# Backplane_v1.net
KiCad netlist of a schematic drawn in EAGLE
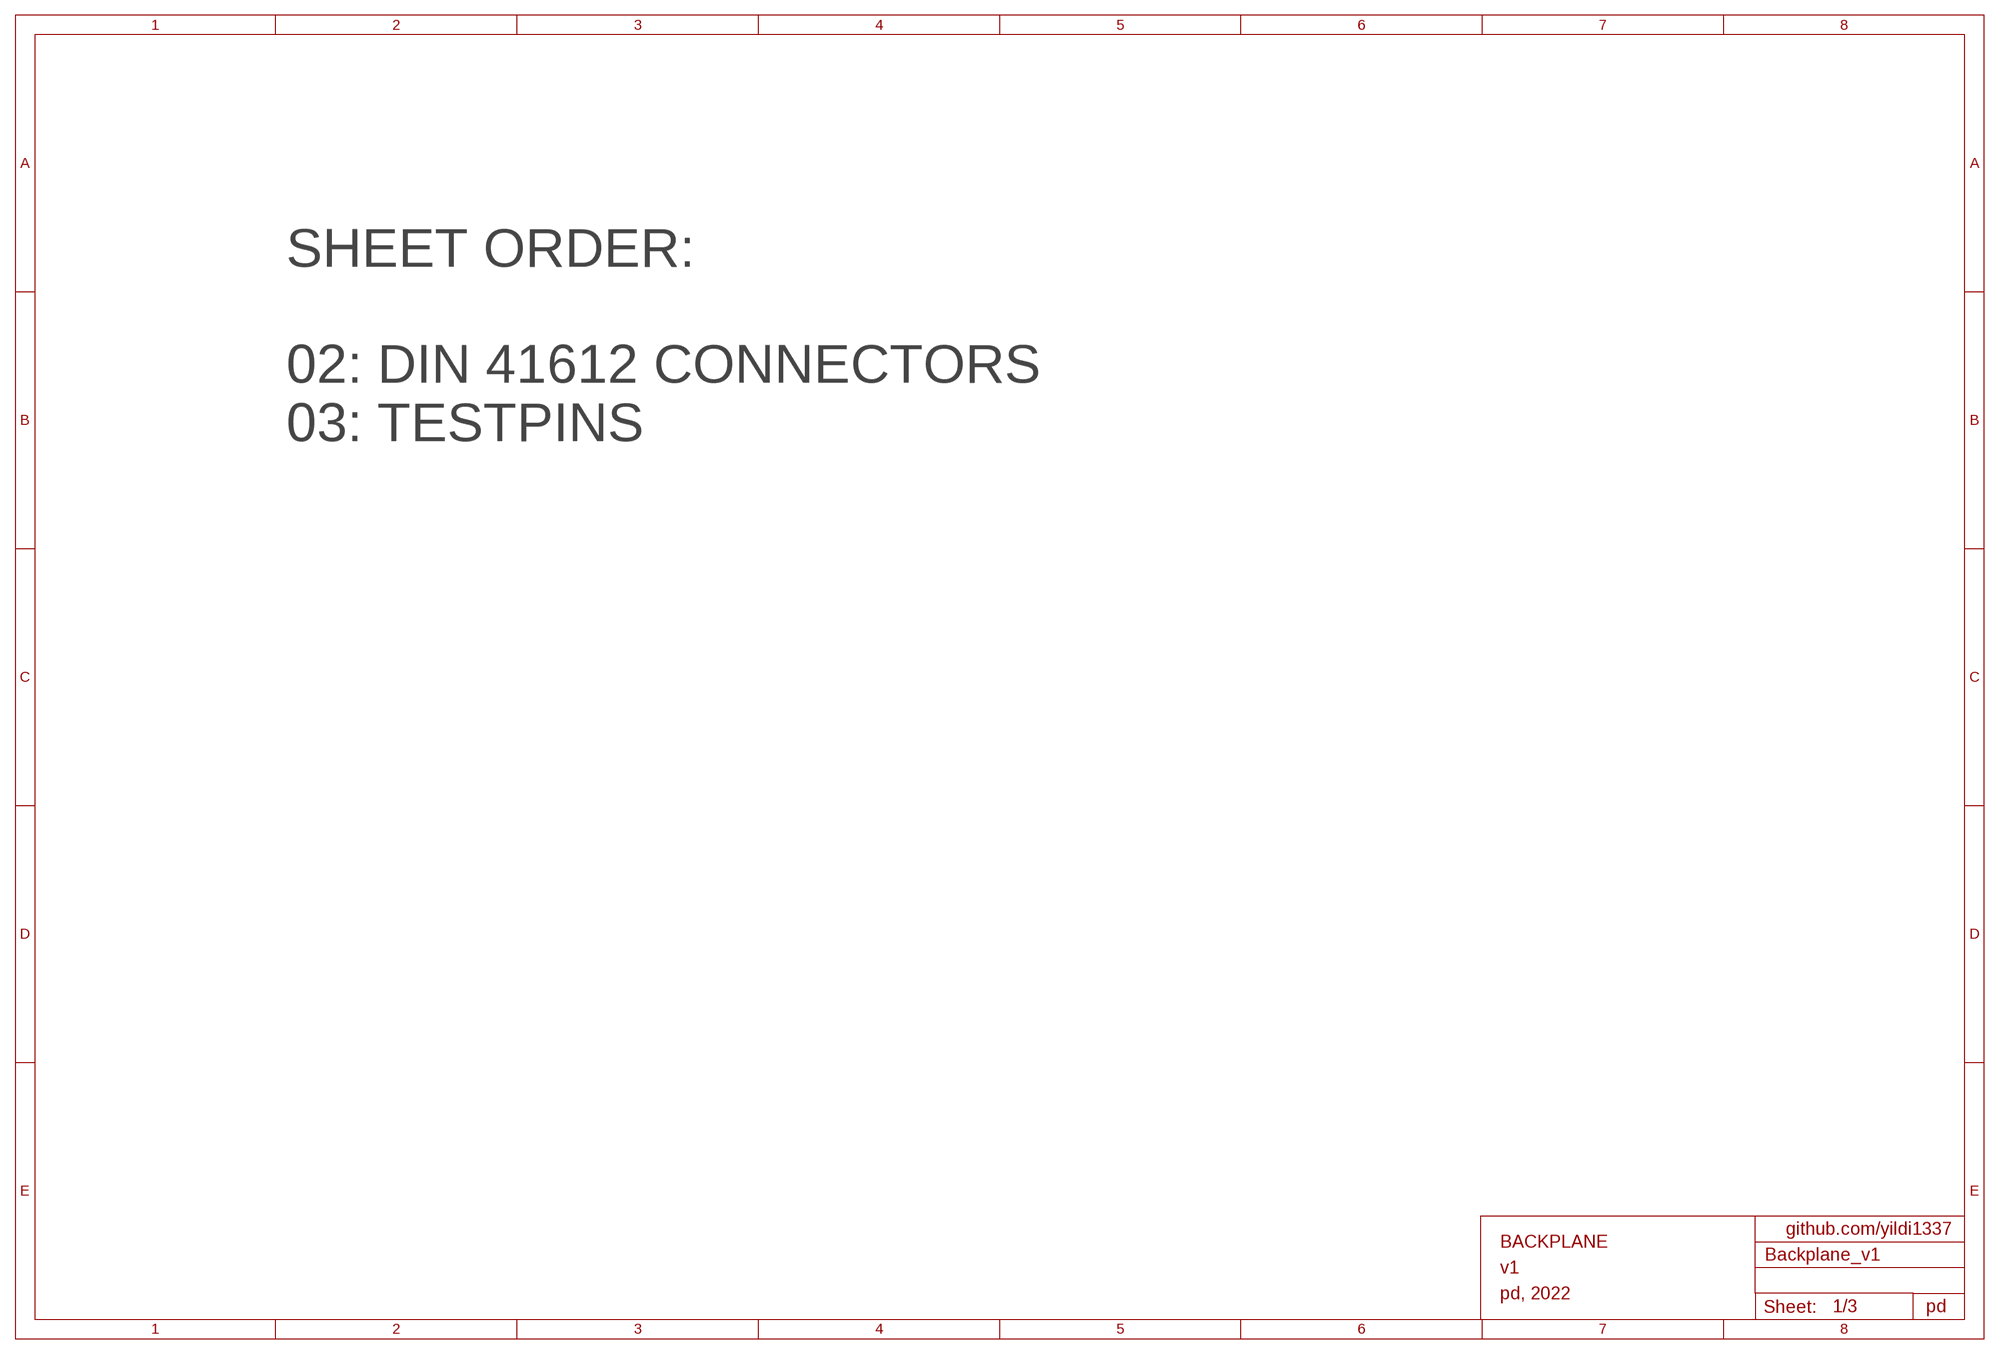
[diagram p0: schematic, sheet 1]
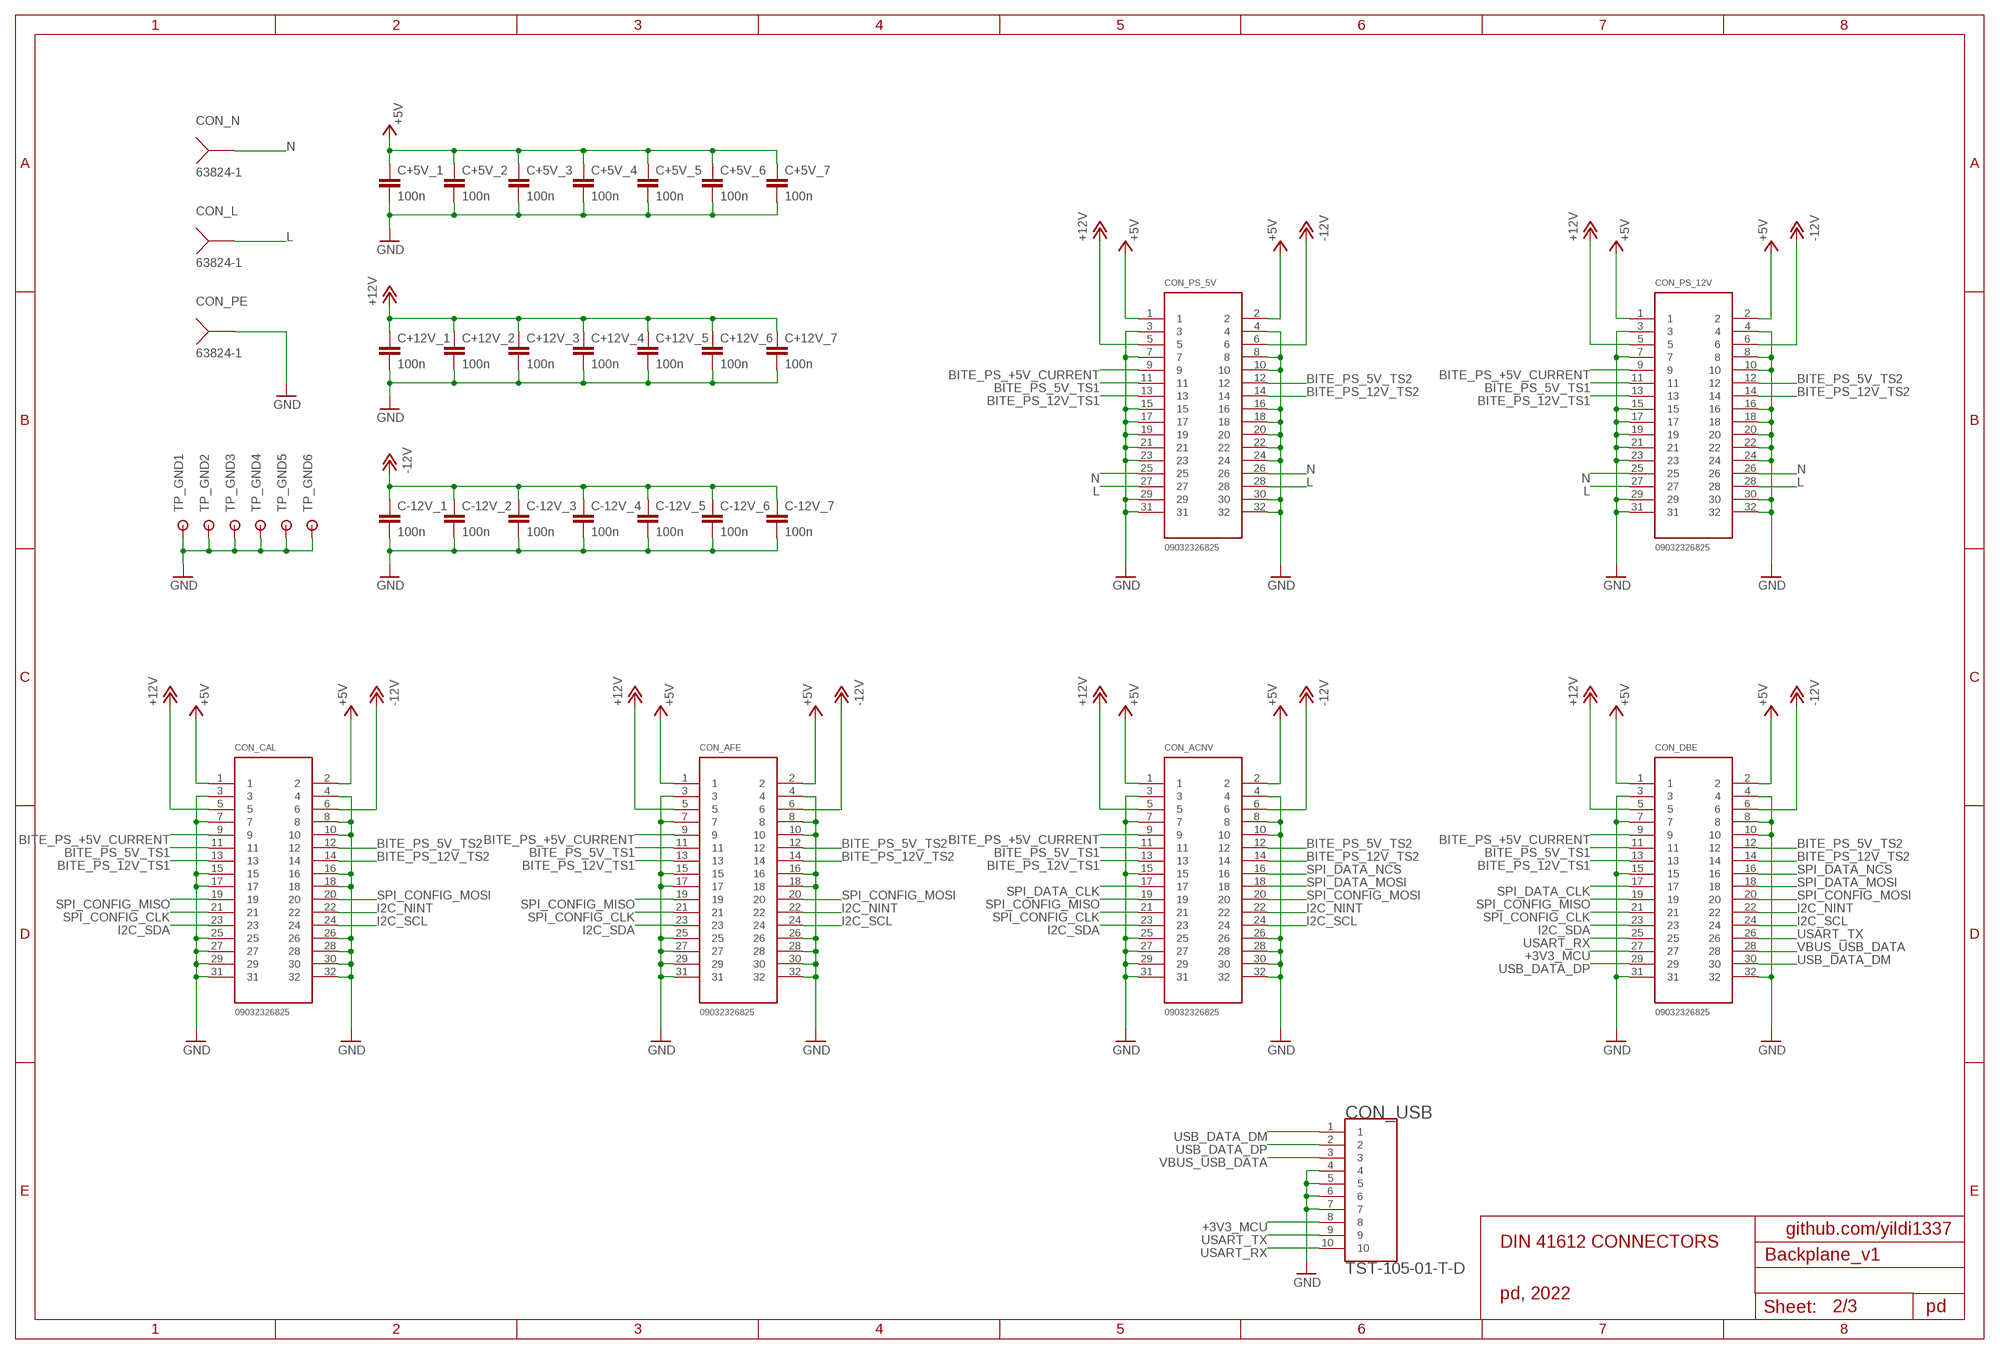
[diagram p1: schematic, sheet 2]
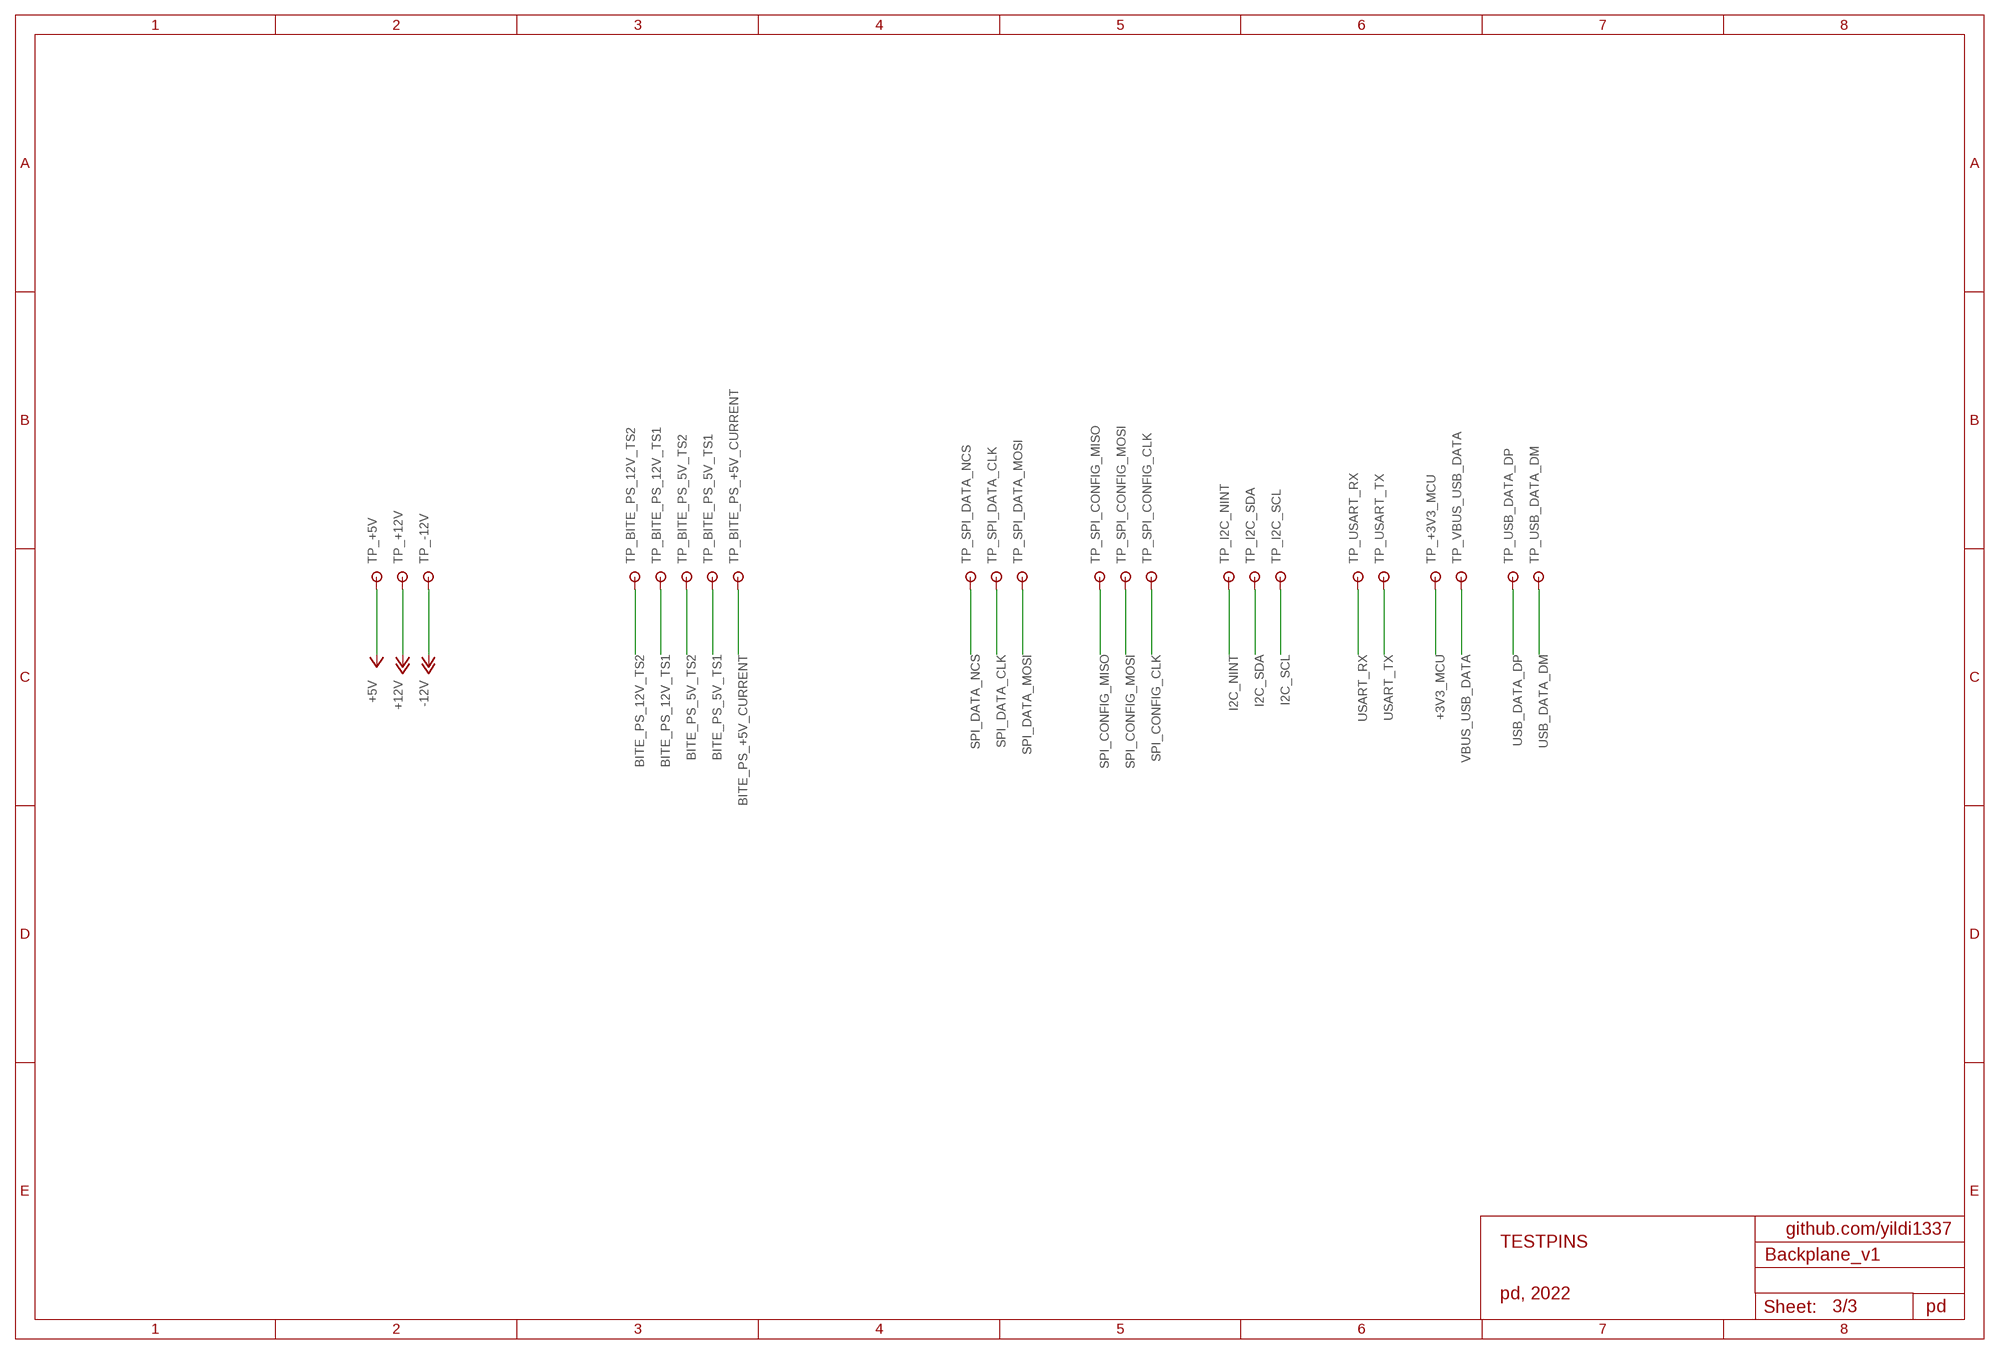
[diagram p2: schematic, sheet 3]

(export (version "E")
  (design (tool "Eeschema 10.0.6"))
  (components
    (comp (ref "C+5V_1")
      (value "100n")
      (footprint "eagle-import:C0603")
      (libsource (lib "eagle-import") (part "C-EUC0603"))
    )
    (comp (ref "C+5V_2")
      (value "100n")
      (footprint "eagle-import:C0603")
      (libsource (lib "eagle-import") (part "C-EUC0603"))
    )
    (comp (ref "C+5V_3")
      (value "100n")
      (footprint "eagle-import:C0603")
      (libsource (lib "eagle-import") (part "C-EUC0603"))
    )
    (comp (ref "C+5V_4")
      (value "100n")
      (footprint "eagle-import:C0603")
      (libsource (lib "eagle-import") (part "C-EUC0603"))
    )
    (comp (ref "C+5V_5")
      (value "100n")
      (footprint "eagle-import:C0603")
      (libsource (lib "eagle-import") (part "C-EUC0603"))
    )
    (comp (ref "C+5V_6")
      (value "100n")
      (footprint "eagle-import:C0603")
      (libsource (lib "eagle-import") (part "C-EUC0603"))
    )
    (comp (ref "C+5V_7")
      (value "100n")
      (footprint "eagle-import:C0603")
      (libsource (lib "eagle-import") (part "C-EUC0603"))
    )
    (comp (ref "C+12V_1")
      (value "100n")
      (footprint "eagle-import:C0603")
      (libsource (lib "eagle-import") (part "C-EUC0603"))
    )
    (comp (ref "C+12V_2")
      (value "100n")
      (footprint "eagle-import:C0603")
      (libsource (lib "eagle-import") (part "C-EUC0603"))
    )
    (comp (ref "C+12V_3")
      (value "100n")
      (footprint "eagle-import:C0603")
      (libsource (lib "eagle-import") (part "C-EUC0603"))
    )
    (comp (ref "C+12V_4")
      (value "100n")
      (footprint "eagle-import:C0603")
      (libsource (lib "eagle-import") (part "C-EUC0603"))
    )
    (comp (ref "C+12V_5")
      (value "100n")
      (footprint "eagle-import:C0603")
      (libsource (lib "eagle-import") (part "C-EUC0603"))
    )
    (comp (ref "C+12V_6")
      (value "100n")
      (footprint "eagle-import:C0603")
      (libsource (lib "eagle-import") (part "C-EUC0603"))
    )
    (comp (ref "C+12V_7")
      (value "100n")
      (footprint "eagle-import:C0603")
      (libsource (lib "eagle-import") (part "C-EUC0603"))
    )
    (comp (ref "C-12V_1")
      (value "100n")
      (footprint "eagle-import:C0603")
      (libsource (lib "eagle-import") (part "C-EUC0603"))
    )
    (comp (ref "C-12V_2")
      (value "100n")
      (footprint "eagle-import:C0603")
      (libsource (lib "eagle-import") (part "C-EUC0603"))
    )
    (comp (ref "C-12V_3")
      (value "100n")
      (footprint "eagle-import:C0603")
      (libsource (lib "eagle-import") (part "C-EUC0603"))
    )
    (comp (ref "C-12V_4")
      (value "100n")
      (footprint "eagle-import:C0603")
      (libsource (lib "eagle-import") (part "C-EUC0603"))
    )
    (comp (ref "C-12V_5")
      (value "100n")
      (footprint "eagle-import:C0603")
      (libsource (lib "eagle-import") (part "C-EUC0603"))
    )
    (comp (ref "C-12V_6")
      (value "100n")
      (footprint "eagle-import:C0603")
      (libsource (lib "eagle-import") (part "C-EUC0603"))
    )
    (comp (ref "C-12V_7")
      (value "100n")
      (footprint "eagle-import:C0603")
      (libsource (lib "eagle-import") (part "C-EUC0603"))
    )
    (comp (ref "CON_ACNV")
      (value "09032326825")
      (footprint "eagle-import:09032326825")
      (libsource (lib "eagle-import") (part "09032326825"))
    )
    (comp (ref "CON_AFE")
      (value "09032326825")
      (footprint "eagle-import:09032326825")
      (libsource (lib "eagle-import") (part "09032326825"))
    )
    (comp (ref "CON_CAL")
      (value "09032326825")
      (footprint "eagle-import:09032326825")
      (libsource (lib "eagle-import") (part "09032326825"))
    )
    (comp (ref "CON_DBE")
      (value "09032326825")
      (footprint "eagle-import:09032326825")
      (libsource (lib "eagle-import") (part "09032326825"))
    )
    (comp (ref "CON_L")
      (value "63824-1")
      (footprint "eagle-import:63824-1")
      (libsource (lib "eagle-import") (part "63824-1"))
    )
    (comp (ref "CON_N")
      (value "63824-1")
      (footprint "eagle-import:63824-1")
      (libsource (lib "eagle-import") (part "63824-1"))
    )
    (comp (ref "CON_PE")
      (value "63824-1")
      (footprint "eagle-import:63824-1")
      (libsource (lib "eagle-import") (part "63824-1"))
    )
    (comp (ref "CON_PS_5V")
      (value "09032326825")
      (footprint "eagle-import:09032326825")
      (libsource (lib "eagle-import") (part "09032326825"))
    )
    (comp (ref "CON_PS_12V")
      (value "09032326825")
      (footprint "eagle-import:09032326825")
      (libsource (lib "eagle-import") (part "09032326825"))
    )
    (comp (ref "CON_USB")
      (value "TST-105-01-T-D")
      (footprint "eagle-import:TST-105-01-T-D")
      (libsource (lib "eagle-import") (part "TST-105-01-T-D"))
    )
    (comp (ref "TP_GND1")
      (value "RSPRO-1MM-TERMINAL-POST-2622034")
      (footprint "eagle-import:RSPRO-1MM-TERMINAL-POST-2622034")
      (libsource (lib "eagle-import") (part "RSPRO-1MM-TERMINAL-POST-2622034"))
    )
    (comp (ref "TP_GND2")
      (value "RSPRO-1MM-TERMINAL-POST-2622034")
      (footprint "eagle-import:RSPRO-1MM-TERMINAL-POST-2622034")
      (libsource (lib "eagle-import") (part "RSPRO-1MM-TERMINAL-POST-2622034"))
    )
    (comp (ref "TP_GND3")
      (value "RSPRO-1MM-TERMINAL-POST-2622034")
      (footprint "eagle-import:RSPRO-1MM-TERMINAL-POST-2622034")
      (libsource (lib "eagle-import") (part "RSPRO-1MM-TERMINAL-POST-2622034"))
    )
    (comp (ref "TP_GND4")
      (value "RSPRO-1MM-TERMINAL-POST-2622034")
      (footprint "eagle-import:RSPRO-1MM-TERMINAL-POST-2622034")
      (libsource (lib "eagle-import") (part "RSPRO-1MM-TERMINAL-POST-2622034"))
    )
    (comp (ref "TP_GND5")
      (value "RSPRO-1MM-TERMINAL-POST-2622034")
      (footprint "eagle-import:RSPRO-1MM-TERMINAL-POST-2622034")
      (libsource (lib "eagle-import") (part "RSPRO-1MM-TERMINAL-POST-2622034"))
    )
    (comp (ref "TP_GND6")
      (value "RSPRO-1MM-TERMINAL-POST-2622034")
      (footprint "eagle-import:RSPRO-1MM-TERMINAL-POST-2622034")
      (libsource (lib "eagle-import") (part "RSPRO-1MM-TERMINAL-POST-2622034"))
    )
    (comp (ref "TP_+3V3_MCU")
      (value "RSPRO-1MM-TERMINAL-POST-2622034")
      (footprint "eagle-import:RSPRO-1MM-TERMINAL-POST-2622034")
      (libsource (lib "eagle-import") (part "RSPRO-1MM-TERMINAL-POST-2622034"))
    )
    (comp (ref "TP_+5V")
      (value "RSPRO-1MM-TERMINAL-POST-2622034")
      (footprint "eagle-import:RSPRO-1MM-TERMINAL-POST-2622034")
      (libsource (lib "eagle-import") (part "RSPRO-1MM-TERMINAL-POST-2622034"))
    )
    (comp (ref "TP_+12V")
      (value "RSPRO-1MM-TERMINAL-POST-2622034")
      (footprint "eagle-import:RSPRO-1MM-TERMINAL-POST-2622034")
      (libsource (lib "eagle-import") (part "RSPRO-1MM-TERMINAL-POST-2622034"))
    )
    (comp (ref "TP_-12V")
      (value "RSPRO-1MM-TERMINAL-POST-2622034")
      (footprint "eagle-import:RSPRO-1MM-TERMINAL-POST-2622034")
      (libsource (lib "eagle-import") (part "RSPRO-1MM-TERMINAL-POST-2622034"))
    )
    (comp (ref "TP_BITE_PS_+5V_CURRENT")
      (value "RSPRO-1MM-TERMINAL-POST-2622034")
      (footprint "eagle-import:RSPRO-1MM-TERMINAL-POST-2622034")
      (libsource (lib "eagle-import") (part "RSPRO-1MM-TERMINAL-POST-2622034"))
    )
    (comp (ref "TP_BITE_PS_5V_TS1")
      (value "RSPRO-1MM-TERMINAL-POST-2622034")
      (footprint "eagle-import:RSPRO-1MM-TERMINAL-POST-2622034")
      (libsource (lib "eagle-import") (part "RSPRO-1MM-TERMINAL-POST-2622034"))
    )
    (comp (ref "TP_BITE_PS_5V_TS2")
      (value "RSPRO-1MM-TERMINAL-POST-2622034")
      (footprint "eagle-import:RSPRO-1MM-TERMINAL-POST-2622034")
      (libsource (lib "eagle-import") (part "RSPRO-1MM-TERMINAL-POST-2622034"))
    )
    (comp (ref "TP_BITE_PS_12V_TS1")
      (value "RSPRO-1MM-TERMINAL-POST-2622034")
      (footprint "eagle-import:RSPRO-1MM-TERMINAL-POST-2622034")
      (libsource (lib "eagle-import") (part "RSPRO-1MM-TERMINAL-POST-2622034"))
    )
    (comp (ref "TP_BITE_PS_12V_TS2")
      (value "RSPRO-1MM-TERMINAL-POST-2622034")
      (footprint "eagle-import:RSPRO-1MM-TERMINAL-POST-2622034")
      (libsource (lib "eagle-import") (part "RSPRO-1MM-TERMINAL-POST-2622034"))
    )
    (comp (ref "TP_I2C_NINT")
      (value "RSPRO-1MM-TERMINAL-POST-2622034")
      (footprint "eagle-import:RSPRO-1MM-TERMINAL-POST-2622034")
      (libsource (lib "eagle-import") (part "RSPRO-1MM-TERMINAL-POST-2622034"))
    )
    (comp (ref "TP_I2C_SCL")
      (value "RSPRO-1MM-TERMINAL-POST-2622034")
      (footprint "eagle-import:RSPRO-1MM-TERMINAL-POST-2622034")
      (libsource (lib "eagle-import") (part "RSPRO-1MM-TERMINAL-POST-2622034"))
    )
    (comp (ref "TP_I2C_SDA")
      (value "RSPRO-1MM-TERMINAL-POST-2622034")
      (footprint "eagle-import:RSPRO-1MM-TERMINAL-POST-2622034")
      (libsource (lib "eagle-import") (part "RSPRO-1MM-TERMINAL-POST-2622034"))
    )
    (comp (ref "TP_SPI_CONFIG_CLK")
      (value "RSPRO-1MM-TERMINAL-POST-2622034")
      (footprint "eagle-import:RSPRO-1MM-TERMINAL-POST-2622034")
      (libsource (lib "eagle-import") (part "RSPRO-1MM-TERMINAL-POST-2622034"))
    )
    (comp (ref "TP_SPI_CONFIG_MISO")
      (value "RSPRO-1MM-TERMINAL-POST-2622034")
      (footprint "eagle-import:RSPRO-1MM-TERMINAL-POST-2622034")
      (libsource (lib "eagle-import") (part "RSPRO-1MM-TERMINAL-POST-2622034"))
    )
    (comp (ref "TP_SPI_CONFIG_MOSI")
      (value "RSPRO-1MM-TERMINAL-POST-2622034")
      (footprint "eagle-import:RSPRO-1MM-TERMINAL-POST-2622034")
      (libsource (lib "eagle-import") (part "RSPRO-1MM-TERMINAL-POST-2622034"))
    )
    (comp (ref "TP_SPI_DATA_CLK")
      (value "RSPRO-1MM-TERMINAL-POST-2622034")
      (footprint "eagle-import:RSPRO-1MM-TERMINAL-POST-2622034")
      (libsource (lib "eagle-import") (part "RSPRO-1MM-TERMINAL-POST-2622034"))
    )
    (comp (ref "TP_SPI_DATA_MOSI")
      (value "RSPRO-1MM-TERMINAL-POST-2622034")
      (footprint "eagle-import:RSPRO-1MM-TERMINAL-POST-2622034")
      (libsource (lib "eagle-import") (part "RSPRO-1MM-TERMINAL-POST-2622034"))
    )
    (comp (ref "TP_SPI_DATA_NCS")
      (value "RSPRO-1MM-TERMINAL-POST-2622034")
      (footprint "eagle-import:RSPRO-1MM-TERMINAL-POST-2622034")
      (libsource (lib "eagle-import") (part "RSPRO-1MM-TERMINAL-POST-2622034"))
    )
    (comp (ref "TP_USART_RX")
      (value "RSPRO-1MM-TERMINAL-POST-2622034")
      (footprint "eagle-import:RSPRO-1MM-TERMINAL-POST-2622034")
      (libsource (lib "eagle-import") (part "RSPRO-1MM-TERMINAL-POST-2622034"))
    )
    (comp (ref "TP_USART_TX")
      (value "RSPRO-1MM-TERMINAL-POST-2622034")
      (footprint "eagle-import:RSPRO-1MM-TERMINAL-POST-2622034")
      (libsource (lib "eagle-import") (part "RSPRO-1MM-TERMINAL-POST-2622034"))
    )
    (comp (ref "TP_USB_DATA_DM")
      (value "RSPRO-1MM-TERMINAL-POST-2622034")
      (footprint "eagle-import:RSPRO-1MM-TERMINAL-POST-2622034")
      (libsource (lib "eagle-import") (part "RSPRO-1MM-TERMINAL-POST-2622034"))
    )
    (comp (ref "TP_USB_DATA_DP")
      (value "RSPRO-1MM-TERMINAL-POST-2622034")
      (footprint "eagle-import:RSPRO-1MM-TERMINAL-POST-2622034")
      (libsource (lib "eagle-import") (part "RSPRO-1MM-TERMINAL-POST-2622034"))
    )
    (comp (ref "TP_VBUS_USB_DATA")
      (value "RSPRO-1MM-TERMINAL-POST-2622034")
      (footprint "eagle-import:RSPRO-1MM-TERMINAL-POST-2622034")
      (libsource (lib "eagle-import") (part "RSPRO-1MM-TERMINAL-POST-2622034"))
    )
  )
  (nets
    (net (code "1") (name "+3V3_MCU") (class "Default")
      (node (ref "CON_DBE") (pin "27") (pinfunction "27_27") (pintype "bidirectional"))
      (node (ref "CON_USB") (pin "8") (pinfunction "8_8") (pintype "passive"))
      (node (ref "TP_+3V3_MCU") (pin "P$1") (pinfunction "P$1_P$1") (pintype "bidirectional"))
    )
    (net (code "2") (name "+5V") (class "Default")
      (node (ref "C+5V_1") (pin "1") (pinfunction "1_1") (pintype "passive"))
      (node (ref "C+5V_2") (pin "1") (pinfunction "1_1") (pintype "passive"))
      (node (ref "C+5V_3") (pin "1") (pinfunction "1_1") (pintype "passive"))
      (node (ref "C+5V_4") (pin "1") (pinfunction "1_1") (pintype "passive"))
      (node (ref "C+5V_5") (pin "1") (pinfunction "1_1") (pintype "passive"))
      (node (ref "C+5V_6") (pin "1") (pinfunction "1_1") (pintype "passive"))
      (node (ref "C+5V_7") (pin "1") (pinfunction "1_1") (pintype "passive"))
      (node (ref "CON_ACNV") (pin "1") (pinfunction "1_1") (pintype "bidirectional"))
      (node (ref "CON_ACNV") (pin "2") (pinfunction "2_2") (pintype "bidirectional"))
      (node (ref "CON_AFE") (pin "1") (pinfunction "1_1") (pintype "bidirectional"))
      (node (ref "CON_AFE") (pin "2") (pinfunction "2_2") (pintype "bidirectional"))
      (node (ref "CON_CAL") (pin "1") (pinfunction "1_1") (pintype "bidirectional"))
      (node (ref "CON_CAL") (pin "2") (pinfunction "2_2") (pintype "bidirectional"))
      (node (ref "CON_DBE") (pin "1") (pinfunction "1_1") (pintype "bidirectional"))
      (node (ref "CON_DBE") (pin "2") (pinfunction "2_2") (pintype "bidirectional"))
      (node (ref "CON_PS_12V") (pin "1") (pinfunction "1_1") (pintype "bidirectional"))
      (node (ref "CON_PS_12V") (pin "2") (pinfunction "2_2") (pintype "bidirectional"))
      (node (ref "CON_PS_5V") (pin "1") (pinfunction "1_1") (pintype "bidirectional"))
      (node (ref "CON_PS_5V") (pin "2") (pinfunction "2_2") (pintype "bidirectional"))
      (node (ref "TP_+5V") (pin "P$1") (pinfunction "P$1_P$1") (pintype "bidirectional"))
    )
    (net (code "3") (name "+12V") (class "Default")
      (node (ref "C+12V_1") (pin "1") (pinfunction "1_1") (pintype "passive"))
      (node (ref "C+12V_2") (pin "1") (pinfunction "1_1") (pintype "passive"))
      (node (ref "C+12V_3") (pin "1") (pinfunction "1_1") (pintype "passive"))
      (node (ref "C+12V_4") (pin "1") (pinfunction "1_1") (pintype "passive"))
      (node (ref "C+12V_5") (pin "1") (pinfunction "1_1") (pintype "passive"))
      (node (ref "C+12V_6") (pin "1") (pinfunction "1_1") (pintype "passive"))
      (node (ref "C+12V_7") (pin "1") (pinfunction "1_1") (pintype "passive"))
      (node (ref "CON_ACNV") (pin "5") (pinfunction "5_5") (pintype "bidirectional"))
      (node (ref "CON_AFE") (pin "5") (pinfunction "5_5") (pintype "bidirectional"))
      (node (ref "CON_CAL") (pin "5") (pinfunction "5_5") (pintype "bidirectional"))
      (node (ref "CON_DBE") (pin "5") (pinfunction "5_5") (pintype "bidirectional"))
      (node (ref "CON_PS_12V") (pin "5") (pinfunction "5_5") (pintype "bidirectional"))
      (node (ref "CON_PS_5V") (pin "5") (pinfunction "5_5") (pintype "bidirectional"))
      (node (ref "TP_+12V") (pin "P$1") (pinfunction "P$1_P$1") (pintype "bidirectional"))
    )
    (net (code "4") (name "-12V") (class "Default")
      (node (ref "C-12V_1") (pin "1") (pinfunction "1_1") (pintype "passive"))
      (node (ref "C-12V_2") (pin "1") (pinfunction "1_1") (pintype "passive"))
      (node (ref "C-12V_3") (pin "1") (pinfunction "1_1") (pintype "passive"))
      (node (ref "C-12V_4") (pin "1") (pinfunction "1_1") (pintype "passive"))
      (node (ref "C-12V_5") (pin "1") (pinfunction "1_1") (pintype "passive"))
      (node (ref "C-12V_6") (pin "1") (pinfunction "1_1") (pintype "passive"))
      (node (ref "C-12V_7") (pin "1") (pinfunction "1_1") (pintype "passive"))
      (node (ref "CON_ACNV") (pin "6") (pinfunction "6_6") (pintype "bidirectional"))
      (node (ref "CON_AFE") (pin "6") (pinfunction "6_6") (pintype "bidirectional"))
      (node (ref "CON_CAL") (pin "6") (pinfunction "6_6") (pintype "bidirectional"))
      (node (ref "CON_DBE") (pin "6") (pinfunction "6_6") (pintype "bidirectional"))
      (node (ref "CON_PS_12V") (pin "6") (pinfunction "6_6") (pintype "bidirectional"))
      (node (ref "CON_PS_5V") (pin "6") (pinfunction "6_6") (pintype "bidirectional"))
      (node (ref "TP_-12V") (pin "P$1") (pinfunction "P$1_P$1") (pintype "bidirectional"))
    )
    (net (code "5") (name "BITE_PS_+5V_CURRENT") (class "Default")
      (node (ref "CON_ACNV") (pin "9") (pinfunction "9_9") (pintype "bidirectional"))
      (node (ref "CON_AFE") (pin "9") (pinfunction "9_9") (pintype "bidirectional"))
      (node (ref "CON_CAL") (pin "9") (pinfunction "9_9") (pintype "bidirectional"))
      (node (ref "CON_DBE") (pin "9") (pinfunction "9_9") (pintype "bidirectional"))
      (node (ref "CON_PS_12V") (pin "9") (pinfunction "9_9") (pintype "bidirectional"))
      (node (ref "CON_PS_5V") (pin "9") (pinfunction "9_9") (pintype "bidirectional"))
      (node (ref "TP_BITE_PS_+5V_CURRENT") (pin "P$1") (pinfunction "P$1_P$1") (pintype "bidirectional"))
    )
    (net (code "6") (name "BITE_PS_5V_TS1") (class "Default")
      (node (ref "CON_ACNV") (pin "11") (pinfunction "11_11") (pintype "bidirectional"))
      (node (ref "CON_AFE") (pin "11") (pinfunction "11_11") (pintype "bidirectional"))
      (node (ref "CON_CAL") (pin "11") (pinfunction "11_11") (pintype "bidirectional"))
      (node (ref "CON_DBE") (pin "11") (pinfunction "11_11") (pintype "bidirectional"))
      (node (ref "CON_PS_12V") (pin "11") (pinfunction "11_11") (pintype "bidirectional"))
      (node (ref "CON_PS_5V") (pin "11") (pinfunction "11_11") (pintype "bidirectional"))
      (node (ref "TP_BITE_PS_5V_TS1") (pin "P$1") (pinfunction "P$1_P$1") (pintype "bidirectional"))
    )
    (net (code "7") (name "BITE_PS_5V_TS2") (class "Default")
      (node (ref "CON_ACNV") (pin "12") (pinfunction "12_12") (pintype "bidirectional"))
      (node (ref "CON_AFE") (pin "12") (pinfunction "12_12") (pintype "bidirectional"))
      (node (ref "CON_CAL") (pin "12") (pinfunction "12_12") (pintype "bidirectional"))
      (node (ref "CON_DBE") (pin "12") (pinfunction "12_12") (pintype "bidirectional"))
      (node (ref "CON_PS_12V") (pin "12") (pinfunction "12_12") (pintype "bidirectional"))
      (node (ref "CON_PS_5V") (pin "12") (pinfunction "12_12") (pintype "bidirectional"))
      (node (ref "TP_BITE_PS_5V_TS2") (pin "P$1") (pinfunction "P$1_P$1") (pintype "bidirectional"))
    )
    (net (code "8") (name "BITE_PS_12V_TS1") (class "Default")
      (node (ref "CON_ACNV") (pin "13") (pinfunction "13_13") (pintype "bidirectional"))
      (node (ref "CON_AFE") (pin "13") (pinfunction "13_13") (pintype "bidirectional"))
      (node (ref "CON_CAL") (pin "13") (pinfunction "13_13") (pintype "bidirectional"))
      (node (ref "CON_DBE") (pin "13") (pinfunction "13_13") (pintype "bidirectional"))
      (node (ref "CON_PS_12V") (pin "13") (pinfunction "13_13") (pintype "bidirectional"))
      (node (ref "CON_PS_5V") (pin "13") (pinfunction "13_13") (pintype "bidirectional"))
      (node (ref "TP_BITE_PS_12V_TS1") (pin "P$1") (pinfunction "P$1_P$1") (pintype "bidirectional"))
    )
    (net (code "9") (name "BITE_PS_12V_TS2") (class "Default")
      (node (ref "CON_ACNV") (pin "14") (pinfunction "14_14") (pintype "bidirectional"))
      (node (ref "CON_AFE") (pin "14") (pinfunction "14_14") (pintype "bidirectional"))
      (node (ref "CON_CAL") (pin "14") (pinfunction "14_14") (pintype "bidirectional"))
      (node (ref "CON_DBE") (pin "14") (pinfunction "14_14") (pintype "bidirectional"))
      (node (ref "CON_PS_12V") (pin "14") (pinfunction "14_14") (pintype "bidirectional"))
      (node (ref "CON_PS_5V") (pin "14") (pinfunction "14_14") (pintype "bidirectional"))
      (node (ref "TP_BITE_PS_12V_TS2") (pin "P$1") (pinfunction "P$1_P$1") (pintype "bidirectional"))
    )
    (net (code "10") (name "GND") (class "Default")
      (node (ref "C+12V_1") (pin "2") (pinfunction "2_2") (pintype "passive"))
      (node (ref "C+12V_2") (pin "2") (pinfunction "2_2") (pintype "passive"))
      (node (ref "C+12V_3") (pin "2") (pinfunction "2_2") (pintype "passive"))
      (node (ref "C+12V_4") (pin "2") (pinfunction "2_2") (pintype "passive"))
      (node (ref "C+12V_5") (pin "2") (pinfunction "2_2") (pintype "passive"))
      (node (ref "C+12V_6") (pin "2") (pinfunction "2_2") (pintype "passive"))
      (node (ref "C+12V_7") (pin "2") (pinfunction "2_2") (pintype "passive"))
      (node (ref "C+5V_1") (pin "2") (pinfunction "2_2") (pintype "passive"))
      (node (ref "C+5V_2") (pin "2") (pinfunction "2_2") (pintype "passive"))
      (node (ref "C+5V_3") (pin "2") (pinfunction "2_2") (pintype "passive"))
      (node (ref "C+5V_4") (pin "2") (pinfunction "2_2") (pintype "passive"))
      (node (ref "C+5V_5") (pin "2") (pinfunction "2_2") (pintype "passive"))
      (node (ref "C+5V_6") (pin "2") (pinfunction "2_2") (pintype "passive"))
      (node (ref "C+5V_7") (pin "2") (pinfunction "2_2") (pintype "passive"))
      (node (ref "C-12V_1") (pin "2") (pinfunction "2_2") (pintype "passive"))
      (node (ref "C-12V_2") (pin "2") (pinfunction "2_2") (pintype "passive"))
      (node (ref "C-12V_3") (pin "2") (pinfunction "2_2") (pintype "passive"))
      (node (ref "C-12V_4") (pin "2") (pinfunction "2_2") (pintype "passive"))
      (node (ref "C-12V_5") (pin "2") (pinfunction "2_2") (pintype "passive"))
      (node (ref "C-12V_6") (pin "2") (pinfunction "2_2") (pintype "passive"))
      (node (ref "C-12V_7") (pin "2") (pinfunction "2_2") (pintype "passive"))
      (node (ref "CON_ACNV") (pin "10") (pinfunction "10_10") (pintype "bidirectional"))
      (node (ref "CON_ACNV") (pin "15") (pinfunction "15_15") (pintype "bidirectional"))
      (node (ref "CON_ACNV") (pin "25") (pinfunction "25_25") (pintype "bidirectional"))
      (node (ref "CON_ACNV") (pin "26") (pinfunction "26_26") (pintype "bidirectional"))
      (node (ref "CON_ACNV") (pin "27") (pinfunction "27_27") (pintype "bidirectional"))
      (node (ref "CON_ACNV") (pin "28") (pinfunction "28_28") (pintype "bidirectional"))
      (node (ref "CON_ACNV") (pin "29") (pinfunction "29_29") (pintype "bidirectional"))
      (node (ref "CON_ACNV") (pin "3") (pinfunction "3_3") (pintype "bidirectional"))
      (node (ref "CON_ACNV") (pin "30") (pinfunction "30_30") (pintype "bidirectional"))
      (node (ref "CON_ACNV") (pin "31") (pinfunction "31_31") (pintype "bidirectional"))
      (node (ref "CON_ACNV") (pin "32") (pinfunction "32_32") (pintype "bidirectional"))
      (node (ref "CON_ACNV") (pin "4") (pinfunction "4_4") (pintype "bidirectional"))
      (node (ref "CON_ACNV") (pin "7") (pinfunction "7_7") (pintype "bidirectional"))
      (node (ref "CON_ACNV") (pin "8") (pinfunction "8_8") (pintype "bidirectional"))
      (node (ref "CON_AFE") (pin "10") (pinfunction "10_10") (pintype "bidirectional"))
      (node (ref "CON_AFE") (pin "15") (pinfunction "15_15") (pintype "bidirectional"))
      (node (ref "CON_AFE") (pin "16") (pinfunction "16_16") (pintype "bidirectional"))
      (node (ref "CON_AFE") (pin "17") (pinfunction "17_17") (pintype "bidirectional"))
      (node (ref "CON_AFE") (pin "18") (pinfunction "18_18") (pintype "bidirectional"))
      (node (ref "CON_AFE") (pin "25") (pinfunction "25_25") (pintype "bidirectional"))
      (node (ref "CON_AFE") (pin "26") (pinfunction "26_26") (pintype "bidirectional"))
      (node (ref "CON_AFE") (pin "27") (pinfunction "27_27") (pintype "bidirectional"))
      (node (ref "CON_AFE") (pin "28") (pinfunction "28_28") (pintype "bidirectional"))
      (node (ref "CON_AFE") (pin "29") (pinfunction "29_29") (pintype "bidirectional"))
      (node (ref "CON_AFE") (pin "3") (pinfunction "3_3") (pintype "bidirectional"))
      (node (ref "CON_AFE") (pin "30") (pinfunction "30_30") (pintype "bidirectional"))
      (node (ref "CON_AFE") (pin "31") (pinfunction "31_31") (pintype "bidirectional"))
      (node (ref "CON_AFE") (pin "32") (pinfunction "32_32") (pintype "bidirectional"))
      (node (ref "CON_AFE") (pin "4") (pinfunction "4_4") (pintype "bidirectional"))
      (node (ref "CON_AFE") (pin "7") (pinfunction "7_7") (pintype "bidirectional"))
      (node (ref "CON_AFE") (pin "8") (pinfunction "8_8") (pintype "bidirectional"))
      (node (ref "CON_CAL") (pin "10") (pinfunction "10_10") (pintype "bidirectional"))
      (node (ref "CON_CAL") (pin "15") (pinfunction "15_15") (pintype "bidirectional"))
      (node (ref "CON_CAL") (pin "16") (pinfunction "16_16") (pintype "bidirectional"))
      (node (ref "CON_CAL") (pin "17") (pinfunction "17_17") (pintype "bidirectional"))
      (node (ref "CON_CAL") (pin "18") (pinfunction "18_18") (pintype "bidirectional"))
      (node (ref "CON_CAL") (pin "25") (pinfunction "25_25") (pintype "bidirectional"))
      (node (ref "CON_CAL") (pin "26") (pinfunction "26_26") (pintype "bidirectional"))
      (node (ref "CON_CAL") (pin "27") (pinfunction "27_27") (pintype "bidirectional"))
      (node (ref "CON_CAL") (pin "28") (pinfunction "28_28") (pintype "bidirectional"))
      (node (ref "CON_CAL") (pin "29") (pinfunction "29_29") (pintype "bidirectional"))
      (node (ref "CON_CAL") (pin "3") (pinfunction "3_3") (pintype "bidirectional"))
      (node (ref "CON_CAL") (pin "30") (pinfunction "30_30") (pintype "bidirectional"))
      (node (ref "CON_CAL") (pin "31") (pinfunction "31_31") (pintype "bidirectional"))
      (node (ref "CON_CAL") (pin "32") (pinfunction "32_32") (pintype "bidirectional"))
      (node (ref "CON_CAL") (pin "4") (pinfunction "4_4") (pintype "bidirectional"))
      (node (ref "CON_CAL") (pin "7") (pinfunction "7_7") (pintype "bidirectional"))
      (node (ref "CON_CAL") (pin "8") (pinfunction "8_8") (pintype "bidirectional"))
      (node (ref "CON_DBE") (pin "10") (pinfunction "10_10") (pintype "bidirectional"))
      (node (ref "CON_DBE") (pin "15") (pinfunction "15_15") (pintype "bidirectional"))
      (node (ref "CON_DBE") (pin "3") (pinfunction "3_3") (pintype "bidirectional"))
      (node (ref "CON_DBE") (pin "31") (pinfunction "31_31") (pintype "bidirectional"))
      (node (ref "CON_DBE") (pin "32") (pinfunction "32_32") (pintype "bidirectional"))
      (node (ref "CON_DBE") (pin "4") (pinfunction "4_4") (pintype "bidirectional"))
      (node (ref "CON_DBE") (pin "7") (pinfunction "7_7") (pintype "bidirectional"))
      (node (ref "CON_DBE") (pin "8") (pinfunction "8_8") (pintype "bidirectional"))
      (node (ref "CON_PE") (pin "1") (pinfunction "1_1") (pintype "passive"))
      (node (ref "CON_PE") (pin "2") (pinfunction "1_2") (pintype "passive"))
      (node (ref "CON_PS_12V") (pin "10") (pinfunction "10_10") (pintype "bidirectional"))
      (node (ref "CON_PS_12V") (pin "15") (pinfunction "15_15") (pintype "bidirectional"))
      (node (ref "CON_PS_12V") (pin "16") (pinfunction "16_16") (pintype "bidirectional"))
      (node (ref "CON_PS_12V") (pin "17") (pinfunction "17_17") (pintype "bidirectional"))
      (node (ref "CON_PS_12V") (pin "18") (pinfunction "18_18") (pintype "bidirectional"))
      (node (ref "CON_PS_12V") (pin "19") (pinfunction "19_19") (pintype "bidirectional"))
      (node (ref "CON_PS_12V") (pin "20") (pinfunction "20_20") (pintype "bidirectional"))
      (node (ref "CON_PS_12V") (pin "21") (pinfunction "21_21") (pintype "bidirectional"))
      (node (ref "CON_PS_12V") (pin "22") (pinfunction "22_22") (pintype "bidirectional"))
      (node (ref "CON_PS_12V") (pin "23") (pinfunction "23_23") (pintype "bidirectional"))
      (node (ref "CON_PS_12V") (pin "24") (pinfunction "24_24") (pintype "bidirectional"))
      (node (ref "CON_PS_12V") (pin "29") (pinfunction "29_29") (pintype "bidirectional"))
      (node (ref "CON_PS_12V") (pin "3") (pinfunction "3_3") (pintype "bidirectional"))
      (node (ref "CON_PS_12V") (pin "30") (pinfunction "30_30") (pintype "bidirectional"))
      (node (ref "CON_PS_12V") (pin "31") (pinfunction "31_31") (pintype "bidirectional"))
      (node (ref "CON_PS_12V") (pin "32") (pinfunction "32_32") (pintype "bidirectional"))
      (node (ref "CON_PS_12V") (pin "4") (pinfunction "4_4") (pintype "bidirectional"))
      (node (ref "CON_PS_12V") (pin "7") (pinfunction "7_7") (pintype "bidirectional"))
      (node (ref "CON_PS_12V") (pin "8") (pinfunction "8_8") (pintype "bidirectional"))
      (node (ref "CON_PS_5V") (pin "10") (pinfunction "10_10") (pintype "bidirectional"))
      (node (ref "CON_PS_5V") (pin "15") (pinfunction "15_15") (pintype "bidirectional"))
      (node (ref "CON_PS_5V") (pin "16") (pinfunction "16_16") (pintype "bidirectional"))
      (node (ref "CON_PS_5V") (pin "17") (pinfunction "17_17") (pintype "bidirectional"))
      (node (ref "CON_PS_5V") (pin "18") (pinfunction "18_18") (pintype "bidirectional"))
      (node (ref "CON_PS_5V") (pin "19") (pinfunction "19_19") (pintype "bidirectional"))
      (node (ref "CON_PS_5V") (pin "20") (pinfunction "20_20") (pintype "bidirectional"))
      (node (ref "CON_PS_5V") (pin "21") (pinfunction "21_21") (pintype "bidirectional"))
      (node (ref "CON_PS_5V") (pin "22") (pinfunction "22_22") (pintype "bidirectional"))
      (node (ref "CON_PS_5V") (pin "23") (pinfunction "23_23") (pintype "bidirectional"))
      (node (ref "CON_PS_5V") (pin "24") (pinfunction "24_24") (pintype "bidirectional"))
      (node (ref "CON_PS_5V") (pin "29") (pinfunction "29_29") (pintype "bidirectional"))
      (node (ref "CON_PS_5V") (pin "3") (pinfunction "3_3") (pintype "bidirectional"))
      (node (ref "CON_PS_5V") (pin "30") (pinfunction "30_30") (pintype "bidirectional"))
      (node (ref "CON_PS_5V") (pin "31") (pinfunction "31_31") (pintype "bidirectional"))
      (node (ref "CON_PS_5V") (pin "32") (pinfunction "32_32") (pintype "bidirectional"))
      (node (ref "CON_PS_5V") (pin "4") (pinfunction "4_4") (pintype "bidirectional"))
      (node (ref "CON_PS_5V") (pin "7") (pinfunction "7_7") (pintype "bidirectional"))
      (node (ref "CON_PS_5V") (pin "8") (pinfunction "8_8") (pintype "bidirectional"))
      (node (ref "CON_USB") (pin "4") (pinfunction "4_4") (pintype "passive"))
      (node (ref "CON_USB") (pin "5") (pinfunction "5_5") (pintype "passive"))
      (node (ref "CON_USB") (pin "6") (pinfunction "6_6") (pintype "passive"))
      (node (ref "CON_USB") (pin "7") (pinfunction "7_7") (pintype "passive"))
      (node (ref "TP_GND1") (pin "P$1") (pinfunction "P$1_P$1") (pintype "bidirectional"))
      (node (ref "TP_GND2") (pin "P$1") (pinfunction "P$1_P$1") (pintype "bidirectional"))
      (node (ref "TP_GND3") (pin "P$1") (pinfunction "P$1_P$1") (pintype "bidirectional"))
      (node (ref "TP_GND4") (pin "P$1") (pinfunction "P$1_P$1") (pintype "bidirectional"))
      (node (ref "TP_GND5") (pin "P$1") (pinfunction "P$1_P$1") (pintype "bidirectional"))
      (node (ref "TP_GND6") (pin "P$1") (pinfunction "P$1_P$1") (pintype "bidirectional"))
    )
    (net (code "11") (name "I2C_NINT") (class "Default")
      (node (ref "CON_ACNV") (pin "22") (pinfunction "22_22") (pintype "bidirectional"))
      (node (ref "CON_AFE") (pin "22") (pinfunction "22_22") (pintype "bidirectional"))
      (node (ref "CON_CAL") (pin "22") (pinfunction "22_22") (pintype "bidirectional"))
      (node (ref "CON_DBE") (pin "22") (pinfunction "22_22") (pintype "bidirectional"))
      (node (ref "TP_I2C_NINT") (pin "P$1") (pinfunction "P$1_P$1") (pintype "bidirectional"))
    )
    (net (code "12") (name "I2C_SCL") (class "Default")
      (node (ref "CON_ACNV") (pin "24") (pinfunction "24_24") (pintype "bidirectional"))
      (node (ref "CON_AFE") (pin "24") (pinfunction "24_24") (pintype "bidirectional"))
      (node (ref "CON_CAL") (pin "24") (pinfunction "24_24") (pintype "bidirectional"))
      (node (ref "CON_DBE") (pin "24") (pinfunction "24_24") (pintype "bidirectional"))
      (node (ref "TP_I2C_SCL") (pin "P$1") (pinfunction "P$1_P$1") (pintype "bidirectional"))
    )
    (net (code "13") (name "I2C_SDA") (class "Default")
      (node (ref "CON_ACNV") (pin "23") (pinfunction "23_23") (pintype "bidirectional"))
      (node (ref "CON_AFE") (pin "23") (pinfunction "23_23") (pintype "bidirectional"))
      (node (ref "CON_CAL") (pin "23") (pinfunction "23_23") (pintype "bidirectional"))
      (node (ref "CON_DBE") (pin "23") (pinfunction "23_23") (pintype "bidirectional"))
      (node (ref "TP_I2C_SDA") (pin "P$1") (pinfunction "P$1_P$1") (pintype "bidirectional"))
    )
    (net (code "14") (name "L") (class "Default")
      (node (ref "CON_L") (pin "1") (pinfunction "1_1") (pintype "passive"))
      (node (ref "CON_L") (pin "2") (pinfunction "1_2") (pintype "passive"))
      (node (ref "CON_PS_12V") (pin "27") (pinfunction "27_27") (pintype "bidirectional"))
      (node (ref "CON_PS_12V") (pin "28") (pinfunction "28_28") (pintype "bidirectional"))
      (node (ref "CON_PS_5V") (pin "27") (pinfunction "27_27") (pintype "bidirectional"))
      (node (ref "CON_PS_5V") (pin "28") (pinfunction "28_28") (pintype "bidirectional"))
    )
    (net (code "15") (name "N") (class "Default")
      (node (ref "CON_N") (pin "1") (pinfunction "1_1") (pintype "passive"))
      (node (ref "CON_N") (pin "2") (pinfunction "1_2") (pintype "passive"))
      (node (ref "CON_PS_12V") (pin "25") (pinfunction "25_25") (pintype "bidirectional"))
      (node (ref "CON_PS_12V") (pin "26") (pinfunction "26_26") (pintype "bidirectional"))
      (node (ref "CON_PS_5V") (pin "25") (pinfunction "25_25") (pintype "bidirectional"))
      (node (ref "CON_PS_5V") (pin "26") (pinfunction "26_26") (pintype "bidirectional"))
    )
    (net (code "16") (name "SPI_CONFIG_CLK") (class "Default")
      (node (ref "CON_ACNV") (pin "21") (pinfunction "21_21") (pintype "bidirectional"))
      (node (ref "CON_AFE") (pin "21") (pinfunction "21_21") (pintype "bidirectional"))
      (node (ref "CON_CAL") (pin "21") (pinfunction "21_21") (pintype "bidirectional"))
      (node (ref "CON_DBE") (pin "21") (pinfunction "21_21") (pintype "bidirectional"))
      (node (ref "TP_SPI_CONFIG_CLK") (pin "P$1") (pinfunction "P$1_P$1") (pintype "bidirectional"))
    )
    (net (code "17") (name "SPI_CONFIG_MISO") (class "Default")
      (node (ref "CON_ACNV") (pin "19") (pinfunction "19_19") (pintype "bidirectional"))
      (node (ref "CON_AFE") (pin "19") (pinfunction "19_19") (pintype "bidirectional"))
      (node (ref "CON_CAL") (pin "19") (pinfunction "19_19") (pintype "bidirectional"))
      (node (ref "CON_DBE") (pin "19") (pinfunction "19_19") (pintype "bidirectional"))
      (node (ref "TP_SPI_CONFIG_MISO") (pin "P$1") (pinfunction "P$1_P$1") (pintype "bidirectional"))
    )
    (net (code "18") (name "SPI_CONFIG_MOSI") (class "Default")
      (node (ref "CON_ACNV") (pin "20") (pinfunction "20_20") (pintype "bidirectional"))
      (node (ref "CON_AFE") (pin "20") (pinfunction "20_20") (pintype "bidirectional"))
      (node (ref "CON_CAL") (pin "20") (pinfunction "20_20") (pintype "bidirectional"))
      (node (ref "CON_DBE") (pin "20") (pinfunction "20_20") (pintype "bidirectional"))
      (node (ref "TP_SPI_CONFIG_MOSI") (pin "P$1") (pinfunction "P$1_P$1") (pintype "bidirectional"))
    )
    (net (code "19") (name "SPI_DATA_CLK") (class "Default")
      (node (ref "CON_ACNV") (pin "17") (pinfunction "17_17") (pintype "bidirectional"))
      (node (ref "CON_DBE") (pin "17") (pinfunction "17_17") (pintype "bidirectional"))
      (node (ref "TP_SPI_DATA_CLK") (pin "P$1") (pinfunction "P$1_P$1") (pintype "bidirectional"))
    )
    (net (code "20") (name "SPI_DATA_MOSI") (class "Default")
      (node (ref "CON_ACNV") (pin "18") (pinfunction "18_18") (pintype "bidirectional"))
      (node (ref "CON_DBE") (pin "18") (pinfunction "18_18") (pintype "bidirectional"))
      (node (ref "TP_SPI_DATA_MOSI") (pin "P$1") (pinfunction "P$1_P$1") (pintype "bidirectional"))
    )
    (net (code "21") (name "SPI_DATA_NCS") (class "Default")
      (node (ref "CON_ACNV") (pin "16") (pinfunction "16_16") (pintype "bidirectional"))
      (node (ref "CON_DBE") (pin "16") (pinfunction "16_16") (pintype "bidirectional"))
      (node (ref "TP_SPI_DATA_NCS") (pin "P$1") (pinfunction "P$1_P$1") (pintype "bidirectional"))
    )
    (net (code "22") (name "USART_RX") (class "Default")
      (node (ref "CON_DBE") (pin "25") (pinfunction "25_25") (pintype "bidirectional"))
      (node (ref "CON_USB") (pin "10") (pinfunction "10_10") (pintype "passive"))
      (node (ref "TP_USART_RX") (pin "P$1") (pinfunction "P$1_P$1") (pintype "bidirectional"))
    )
    (net (code "23") (name "USART_TX") (class "Default")
      (node (ref "CON_DBE") (pin "26") (pinfunction "26_26") (pintype "bidirectional"))
      (node (ref "CON_USB") (pin "9") (pinfunction "9_9") (pintype "passive"))
      (node (ref "TP_USART_TX") (pin "P$1") (pinfunction "P$1_P$1") (pintype "bidirectional"))
    )
    (net (code "24") (name "USB_DATA_DM") (class "Default")
      (node (ref "CON_DBE") (pin "30") (pinfunction "30_30") (pintype "bidirectional"))
      (node (ref "CON_USB") (pin "1") (pinfunction "1_1") (pintype "passive"))
      (node (ref "TP_USB_DATA_DM") (pin "P$1") (pinfunction "P$1_P$1") (pintype "bidirectional"))
    )
    (net (code "25") (name "USB_DATA_DP") (class "Default")
      (node (ref "CON_DBE") (pin "29") (pinfunction "29_29") (pintype "bidirectional"))
      (node (ref "CON_USB") (pin "2") (pinfunction "2_2") (pintype "passive"))
      (node (ref "TP_USB_DATA_DP") (pin "P$1") (pinfunction "P$1_P$1") (pintype "bidirectional"))
    )
    (net (code "26") (name "VBUS_USB_DATA") (class "Default")
      (node (ref "CON_DBE") (pin "28") (pinfunction "28_28") (pintype "bidirectional"))
      (node (ref "CON_USB") (pin "3") (pinfunction "3_3") (pintype "passive"))
      (node (ref "TP_VBUS_USB_DATA") (pin "P$1") (pinfunction "P$1_P$1") (pintype "bidirectional"))
    )
  )
)
